# SmartWatch_System.net
KiCad netlist of a schematic drawn in EAGLE
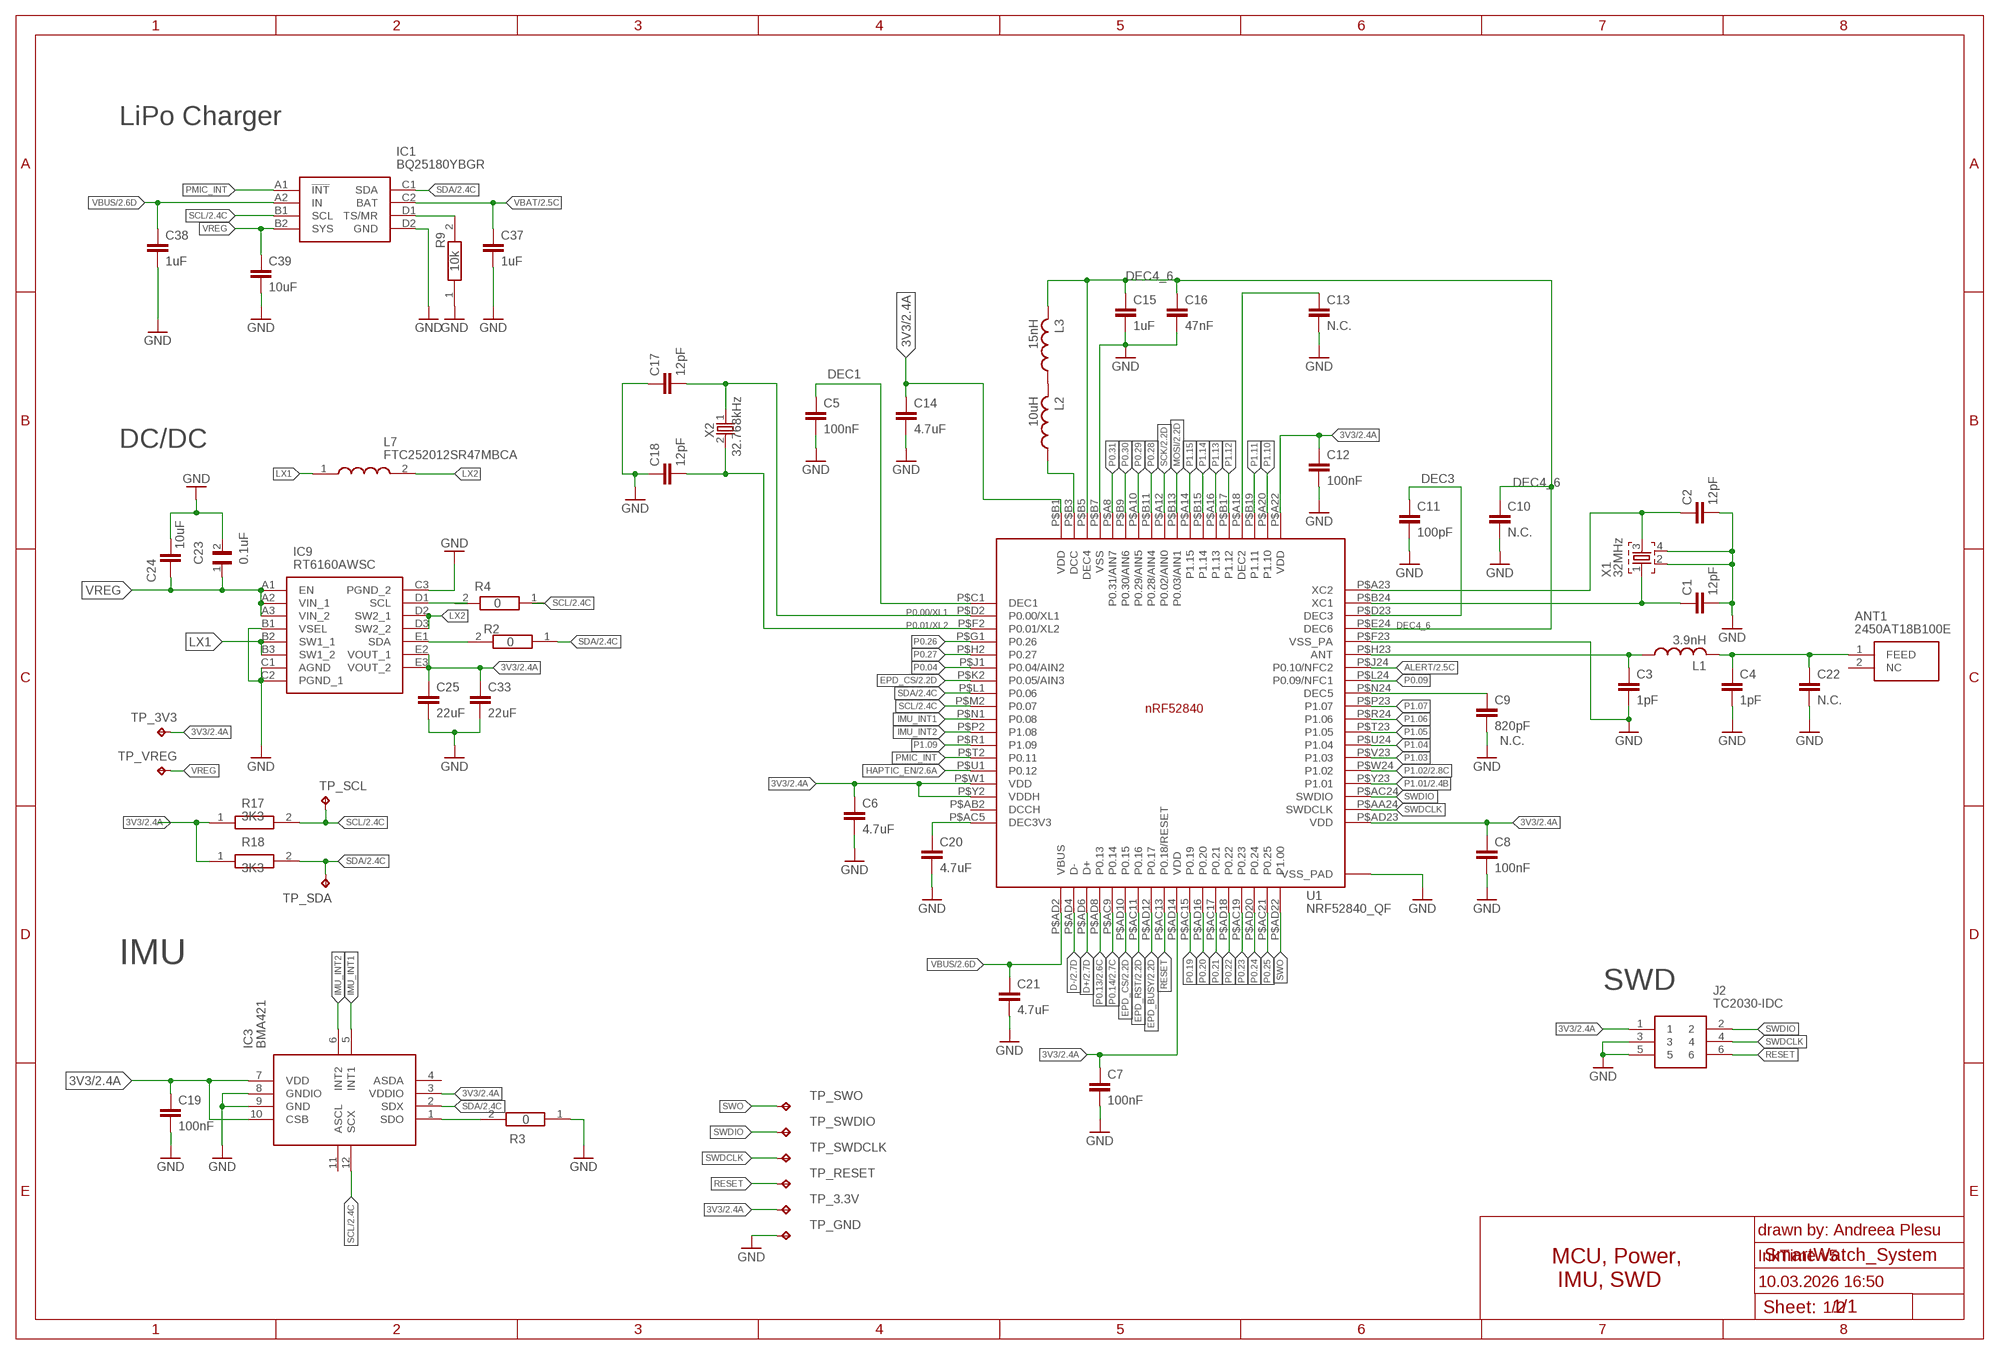
[diagram p0: schematic, sheet 1, part 1 of 2]
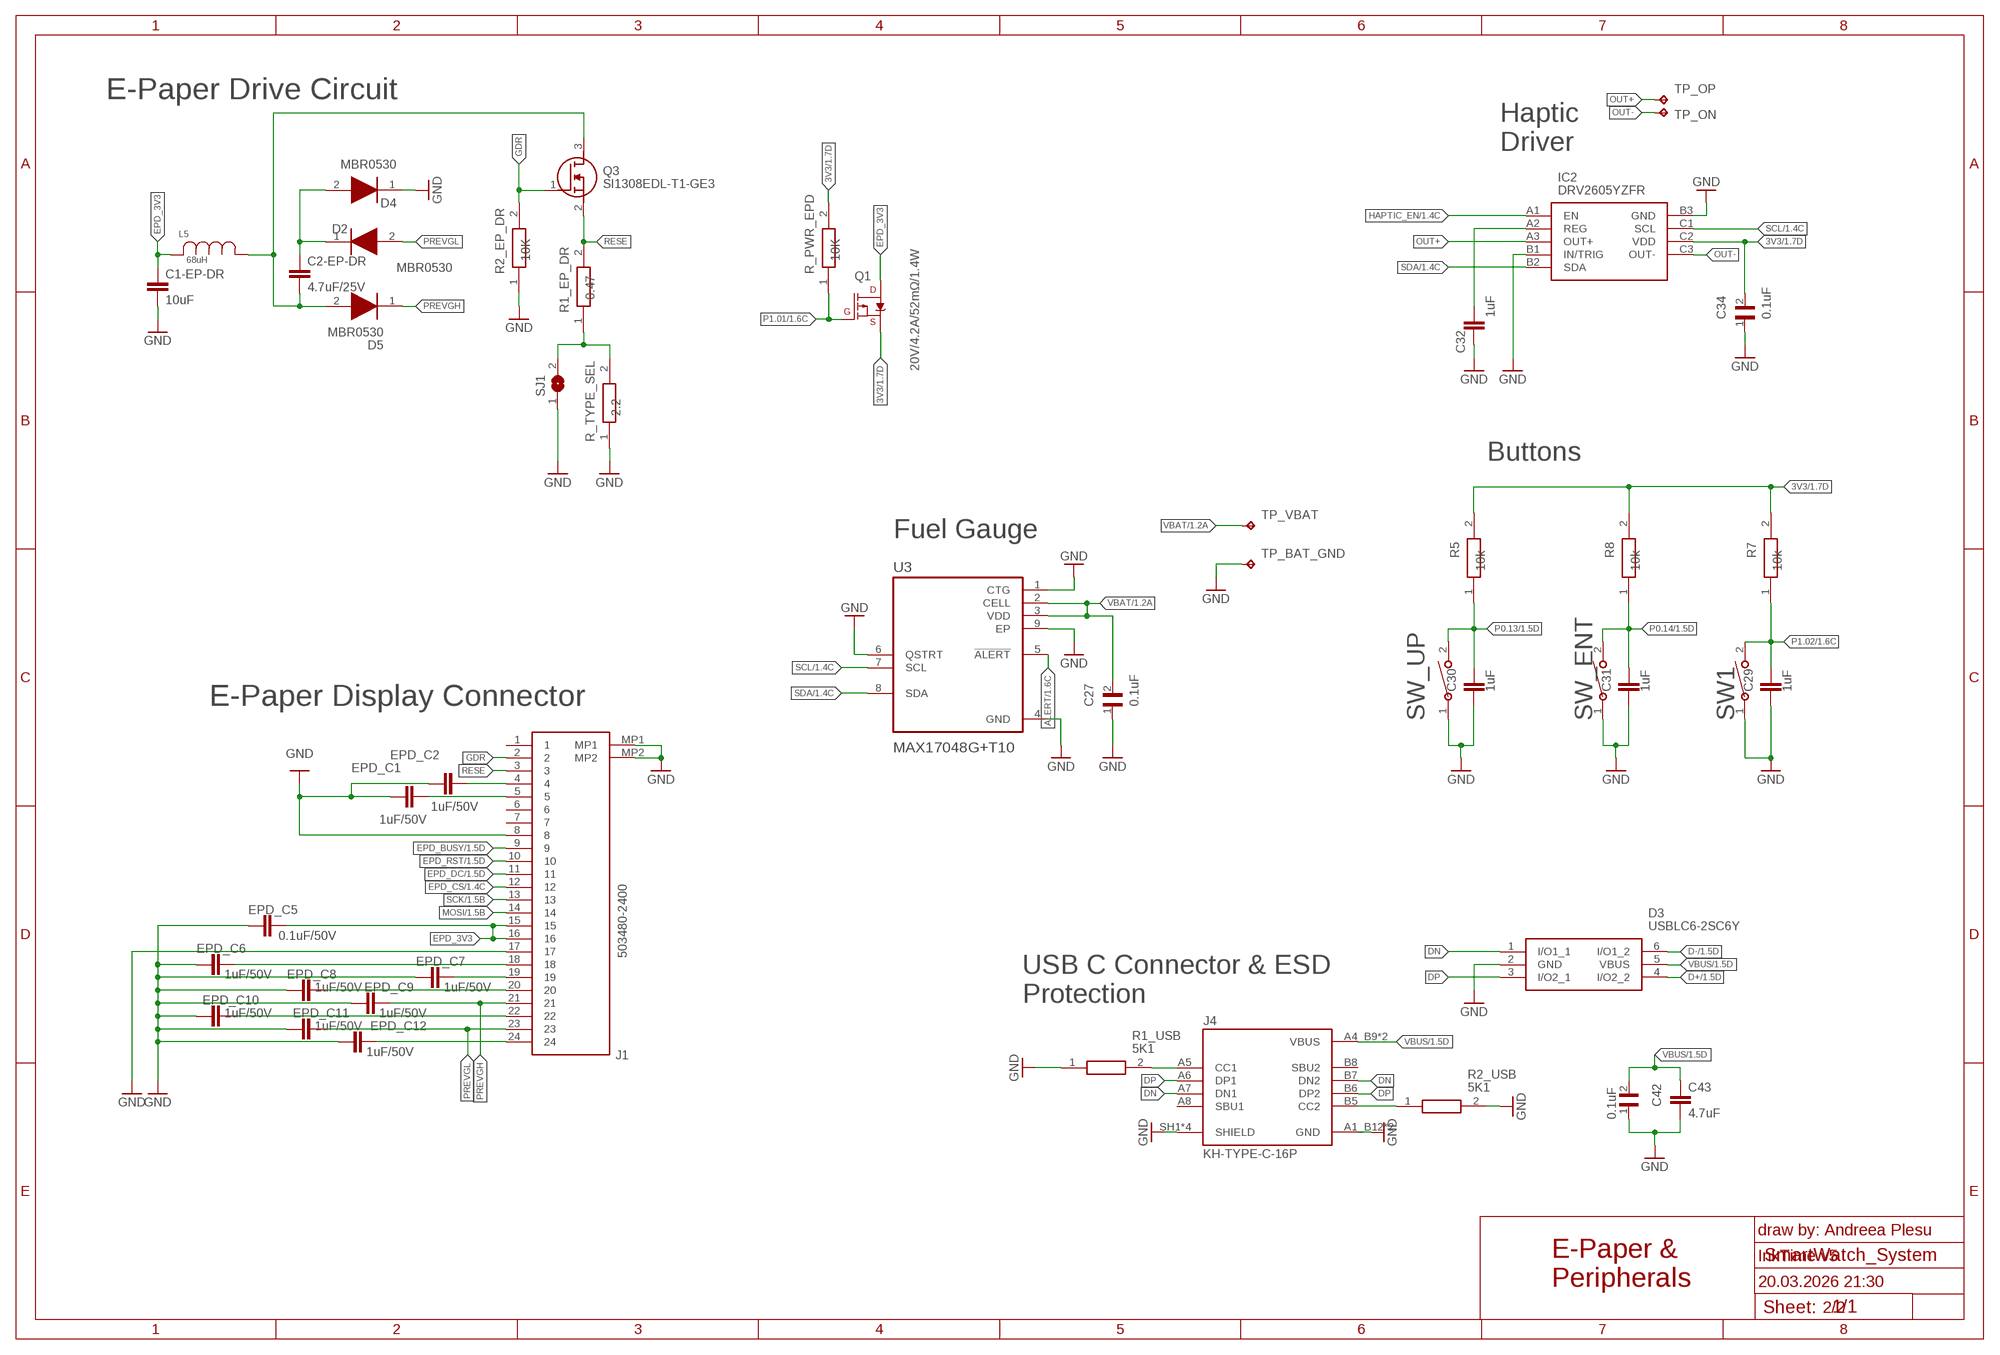
[diagram p1: schematic, sheet 1, part 2 of 2]

(export (version "E")
  (design (tool "Eeschema 10.0.6"))
  (components
    (comp (ref "ANT1")
      (value "2450AT18B100E")
      (footprint "eagle-import:2450AT18B100E_ANTC3216X140N")
      (fields (field (name "MOUSER_PART_NUMBER") "609-2450AT18B100E"))
      (libsource (lib "eagle-import") (part "2450AT18B100E_2450AT18B100E"))
    )
    (comp (ref "C1")
      (value "12pF")
      (footprint "eagle-import:NORDIC_NRF_3_RESC0201_L")
      (libsource (lib "eagle-import") (part "NORDIC_NRF_3_CAPACITOR_0201_L"))
    )
    (comp (ref "C1-EP-DR")
      (value "10uF")
      (footprint "eagle-import:NORDIC_NRF_3_RESC0402_L")
      (libsource (lib "eagle-import") (part "NORDIC_NRF_3_CAPACITOR_0402_L"))
    )
    (comp (ref "C2")
      (value "12pF")
      (footprint "eagle-import:NORDIC_NRF_3_RESC0201_L")
      (libsource (lib "eagle-import") (part "NORDIC_NRF_3_CAPACITOR_0201_L"))
    )
    (comp (ref "C2-EP-DR")
      (value "4.7uF/25V")
      (footprint "eagle-import:NORDIC_NRF_3_RESC0402_L")
      (libsource (lib "eagle-import") (part "NORDIC_NRF_3_CAPACITOR_0402_L"))
    )
    (comp (ref "C3")
      (value "1pF")
      (footprint "eagle-import:NORDIC_NRF_3_RESC0201_L")
      (libsource (lib "eagle-import") (part "NORDIC_NRF_3_CAPACITOR_0201_L"))
    )
    (comp (ref "C4")
      (value "1pF")
      (footprint "eagle-import:NORDIC_NRF_3_RESC0201_L")
      (libsource (lib "eagle-import") (part "NORDIC_NRF_3_CAPACITOR_0201_L"))
    )
    (comp (ref "C5")
      (value "100nF")
      (footprint "eagle-import:NORDIC_NRF_3_RESC0201_L")
      (libsource (lib "eagle-import") (part "NORDIC_NRF_3_CAPACITOR_0201_L"))
    )
    (comp (ref "C6")
      (value "4.7uF")
      (footprint "eagle-import:NORDIC_NRF_3_RESC0402_L")
      (libsource (lib "eagle-import") (part "NORDIC_NRF_3_CAPACITOR_0402_L"))
    )
    (comp (ref "C7")
      (value "100nF")
      (footprint "eagle-import:NORDIC_NRF_3_RESC0201_L")
      (libsource (lib "eagle-import") (part "NORDIC_NRF_3_CAPACITOR_0201_L"))
    )
    (comp (ref "C8")
      (value "100nF")
      (footprint "eagle-import:NORDIC_NRF_3_RESC0201_L")
      (libsource (lib "eagle-import") (part "NORDIC_NRF_3_CAPACITOR_0201_L"))
    )
    (comp (ref "C9")
      (value "820pF")
      (footprint "eagle-import:NORDIC_NRF_3_RESC0201_L")
      (libsource (lib "eagle-import") (part "NORDIC_NRF_3_CAPACITOR_0201_L"))
    )
    (comp (ref "C10")
      (value "N.C.")
      (footprint "eagle-import:NORDIC_NRF_3_RESC0201_L")
      (libsource (lib "eagle-import") (part "NORDIC_NRF_3_CAPACITOR_0201_L"))
    )
    (comp (ref "C11")
      (value "100pF")
      (footprint "eagle-import:NORDIC_NRF_3_RESC0201_L")
      (libsource (lib "eagle-import") (part "NORDIC_NRF_3_CAPACITOR_0201_L"))
    )
    (comp (ref "C12")
      (value "100nF")
      (footprint "eagle-import:NORDIC_NRF_3_RESC0201_L")
      (libsource (lib "eagle-import") (part "NORDIC_NRF_3_CAPACITOR_0201_L"))
    )
    (comp (ref "C13")
      (value "N.C.")
      (footprint "eagle-import:NORDIC_NRF_3_RESC0201_L")
      (libsource (lib "eagle-import") (part "NORDIC_NRF_3_CAPACITOR_0201_L"))
    )
    (comp (ref "C14")
      (value "4.7uF")
      (footprint "eagle-import:PERFECT_0402_0402")
      (libsource (lib "eagle-import") (part "PERFECT_0402_CAP_0402"))
    )
    (comp (ref "C15")
      (value "1uF")
      (footprint "eagle-import:PERFECT_0402_0402")
      (libsource (lib "eagle-import") (part "PERFECT_0402_CAP_0402"))
    )
    (comp (ref "C16")
      (value "47nF")
      (footprint "eagle-import:NORDIC_NRF_3_RESC0201_L")
      (libsource (lib "eagle-import") (part "NORDIC_NRF_3_CAPACITOR_0201_L"))
    )
    (comp (ref "C17")
      (value "12pF")
      (footprint "eagle-import:NORDIC_NRF_3_RESC0201_L")
      (libsource (lib "eagle-import") (part "NORDIC_NRF_3_CAPACITOR_0201_L"))
    )
    (comp (ref "C18")
      (value "12pF")
      (footprint "eagle-import:NORDIC_NRF_3_RESC0201_L")
      (libsource (lib "eagle-import") (part "NORDIC_NRF_3_CAPACITOR_0201_L"))
    )
    (comp (ref "C19")
      (value "100nF")
      (footprint "eagle-import:NORDIC_NRF_3_RESC0201_L")
      (libsource (lib "eagle-import") (part "NORDIC_NRF_3_CAPACITOR_0201_L"))
    )
    (comp (ref "C20")
      (value "4.7uF")
      (footprint "eagle-import:NORDIC_NRF_3_RESC0402_L")
      (libsource (lib "eagle-import") (part "NORDIC_NRF_3_CAPACITOR_0402_L"))
    )
    (comp (ref "C21")
      (value "4.7uF")
      (footprint "eagle-import:NORDIC_NRF_3_RESC0402_L")
      (libsource (lib "eagle-import") (part "NORDIC_NRF_3_CAPACITOR_0402_L"))
    )
    (comp (ref "C22")
      (value "N.C.")
      (footprint "eagle-import:NORDIC_NRF_3_RESC0201_L")
      (libsource (lib "eagle-import") (part "NORDIC_NRF_3_CAPACITOR_0201_L"))
    )
    (comp (ref "C23")
      (value "0.1uF")
      (footprint "eagle-import:GRM011R60J152KE01L_2_CAPC0201X13N")
      (fields (field (name "MF") "Murata") (field (name "MP") "GRM011R60J152KE01L"))
      (libsource (lib "eagle-import") (part "GRM011R60J152KE01L_2_GRM011R60J152KE01L"))
    )
    (comp (ref "C24")
      (value "10uF")
      (footprint "eagle-import:PERFECT_0402_0402")
      (libsource (lib "eagle-import") (part "PERFECT_0402_CAP_0402"))
    )
    (comp (ref "C25")
      (value "22uF")
      (footprint "eagle-import:NORDIC_NRF_3_RESC0402_L")
      (libsource (lib "eagle-import") (part "NORDIC_NRF_3_CAPACITOR_0402_L"))
    )
    (comp (ref "C27")
      (value "0.1uF")
      (footprint "eagle-import:GRM011R60J152KE01L_2_CAPC0201X13N")
      (fields (field (name "MF") "Murata") (field (name "MP") "GRM011R60J152KE01L"))
      (libsource (lib "eagle-import") (part "GRM011R60J152KE01L_2_GRM011R60J152KE01L"))
    )
    (comp (ref "C29")
      (value "1uF")
      (footprint "eagle-import:PERFECT_0402_0402")
      (libsource (lib "eagle-import") (part "PERFECT_0402_CAP_0402"))
    )
    (comp (ref "C30")
      (value "1uF")
      (footprint "eagle-import:PERFECT_0402_0402")
      (libsource (lib "eagle-import") (part "PERFECT_0402_CAP_0402"))
    )
    (comp (ref "C31")
      (value "1uF")
      (footprint "eagle-import:PERFECT_0402_0402")
      (libsource (lib "eagle-import") (part "PERFECT_0402_CAP_0402"))
    )
    (comp (ref "C32")
      (value "1uF")
      (footprint "eagle-import:NORDIC_NRF_3_RESC0402_L")
      (libsource (lib "eagle-import") (part "NORDIC_NRF_3_CAPACITOR_0402_L"))
    )
    (comp (ref "C33")
      (value "22uF")
      (footprint "eagle-import:NORDIC_NRF_3_RESC0402_L")
      (libsource (lib "eagle-import") (part "NORDIC_NRF_3_CAPACITOR_0402_L"))
    )
    (comp (ref "C34")
      (value "0.1uF")
      (footprint "eagle-import:NORDIC_NRF_3_RESC0201_L")
      (libsource (lib "eagle-import") (part "GRM011R60J152KE01L_1_GRM011R60J152KE01L"))
    )
    (comp (ref "C37")
      (value "1uF")
      (footprint "eagle-import:PERFECT_0402_0402")
      (libsource (lib "eagle-import") (part "PERFECT_0402_CAP_0402"))
    )
    (comp (ref "C38")
      (value "1uF")
      (footprint "eagle-import:PERFECT_0402_0402")
      (libsource (lib "eagle-import") (part "PERFECT_0402_CAP_0402"))
    )
    (comp (ref "C39")
      (value "10uF")
      (footprint "eagle-import:PERFECT_0402_0402")
      (libsource (lib "eagle-import") (part "PERFECT_0402_CAP_0402"))
    )
    (comp (ref "C42")
      (value "0.1uF")
      (footprint "eagle-import:NORDIC_NRF_3_RESC0201_L")
      (libsource (lib "eagle-import") (part "GRM011R60J152KE01L_1_GRM011R60J152KE01L"))
    )
    (comp (ref "C43")
      (value "4.7uF")
      (footprint "eagle-import:PERFECT_0402_0402")
      (libsource (lib "eagle-import") (part "PERFECT_0402_CAP_0402"))
    )
    (comp (ref "D2")
      (value "MBR0530")
      (footprint "eagle-import:ESP32_C6_LIBRARY_5_SOD3716X135N")
      (fields (field (name "MF") "ON Semiconductor"))
      (libsource (lib "eagle-import") (part "ESP32_C6_LIBRARY_5_MBR0530"))
    )
    (comp (ref "D3")
      (value "USBLC6-2SC6Y")
      (footprint "eagle-import:ESP32_C6_LIBRARY_3_SOT95P280X145-6N")
      (fields (field (name "MF") "STMicroelectronics"))
      (libsource (lib "eagle-import") (part "ESP32_C6_LIBRARY_3_USBLC6-2SC6Y"))
    )
    (comp (ref "D4")
      (value "MBR0530")
      (footprint "eagle-import:ESP32_C6_LIBRARY_5_SOD3716X135N")
      (fields (field (name "MF") "ON Semiconductor"))
      (libsource (lib "eagle-import") (part "ESP32_C6_LIBRARY_5_MBR0530"))
    )
    (comp (ref "D5")
      (value "MBR0530")
      (footprint "eagle-import:ESP32_C6_LIBRARY_5_SOD3716X135N")
      (fields (field (name "MF") "ON Semiconductor"))
      (libsource (lib "eagle-import") (part "ESP32_C6_LIBRARY_5_MBR0530"))
    )
    (comp (ref "EPD_C1")
      (value "1uF/50V")
      (footprint "eagle-import:NORDIC_NRF_3_RESC0402_L")
      (libsource (lib "eagle-import") (part "NORDIC_NRF_3_CAPACITOR_0402_L"))
    )
    (comp (ref "EPD_C2")
      (value "1uF/50V")
      (footprint "eagle-import:NORDIC_NRF_3_RESC0402_L")
      (libsource (lib "eagle-import") (part "NORDIC_NRF_3_CAPACITOR_0402_L"))
    )
    (comp (ref "EPD_C5")
      (value "0.1uF/50V")
      (footprint "eagle-import:NORDIC_NRF_3_RESC0201_L")
      (libsource (lib "eagle-import") (part "NORDIC_NRF_3_CAPACITOR_0201_L"))
    )
    (comp (ref "EPD_C6")
      (value "1uF/50V")
      (footprint "eagle-import:NORDIC_NRF_3_RESC0402_L")
      (libsource (lib "eagle-import") (part "NORDIC_NRF_3_CAPACITOR_0402_L"))
    )
    (comp (ref "EPD_C7")
      (value "1uF/50V")
      (footprint "eagle-import:NORDIC_NRF_3_RESC0402_L")
      (libsource (lib "eagle-import") (part "NORDIC_NRF_3_CAPACITOR_0402_L"))
    )
    (comp (ref "EPD_C8")
      (value "1uF/50V")
      (footprint "eagle-import:NORDIC_NRF_3_RESC0402_L")
      (libsource (lib "eagle-import") (part "NORDIC_NRF_3_CAPACITOR_0402_L"))
    )
    (comp (ref "EPD_C9")
      (value "1uF/50V")
      (footprint "eagle-import:NORDIC_NRF_3_RESC0402_L")
      (libsource (lib "eagle-import") (part "NORDIC_NRF_3_CAPACITOR_0402_L"))
    )
    (comp (ref "EPD_C10")
      (value "1uF/50V")
      (footprint "eagle-import:NORDIC_NRF_3_RESC0402_L")
      (libsource (lib "eagle-import") (part "NORDIC_NRF_3_CAPACITOR_0402_L"))
    )
    (comp (ref "EPD_C11")
      (value "1uF/50V")
      (footprint "eagle-import:NORDIC_NRF_3_RESC0402_L")
      (libsource (lib "eagle-import") (part "NORDIC_NRF_3_CAPACITOR_0402_L"))
    )
    (comp (ref "EPD_C12")
      (value "1uF/50V")
      (footprint "eagle-import:NORDIC_NRF_3_RESC0402_L")
      (libsource (lib "eagle-import") (part "NORDIC_NRF_3_CAPACITOR_0402_L"))
    )
    (comp (ref "IC1")
      (value "BQ25180YBGR")
      (footprint "eagle-import:BQ25180YBGR_BGA8C40P2X4_100X155X50")
      (fields (field (name "MOUSER_PART_NUMBER") "595-BQ25180YBGR"))
      (libsource (lib "eagle-import") (part "BQ25180YBGR_BQ25180YBGR"))
    )
    (comp (ref "IC2")
      (value "DRV2605YZFR")
      (footprint "eagle-import:DRV2605YZFR_BGA9C50P3X3_144X144X62")
      (libsource (lib "eagle-import") (part "DRV2605YZFR_DRV2605YZFR"))
    )
    (comp (ref "IC3")
      (value "BMA421")
      (footprint "eagle-import:BMA423_BMA423")
      (fields (field (name "ARROW_PART_NUMBER") "BMA423") (field (name "MOUSER_PART_NUMBER") "262-BMA423"))
      (libsource (lib "eagle-import") (part "BMA423_BMA423"))
    )
    (comp (ref "IC9")
      (value "RT6160AWSC")
      (footprint "eagle-import:RT6160AWSC_BGA15C40P3X5_140X230X60")
      (fields (field (name "MOUSER_PART_NUMBER") "835-RT6160AWSC"))
      (libsource (lib "eagle-import") (part "RT6160AWSC_RT6160AWSC"))
    )
    (comp (ref "J1")
      (value "503480-2400")
      (footprint "eagle-import:503480-2400_5034802400")
      (fields (field (name "MOUSER_PART_NUMBER") "538-503480-2400"))
      (libsource (lib "eagle-import") (part "503480-2400_503480-2400"))
    )
    (comp (ref "J2")
      (value "TC2030-IDC")
      (footprint "eagle-import:TC2030-IDC_TC2030IDC")
      (libsource (lib "eagle-import") (part "TC2030-IDC_TC2030-IDC"))
    )
    (comp (ref "J4")
      (value "KH-TYPE-C-16P")
      (footprint "eagle-import:KH-TYPE-C-16P_KINGHELM_KH-TYPE-C-16P")
      (fields (field (name "MF") "kinghelm"))
      (libsource (lib "eagle-import") (part "KH-TYPE-C-16P_KH-TYPE-C-16P"))
    )
    (comp (ref "L1")
      (value "3.9nH")
      (footprint "eagle-import:NORDIC_NRF_2_RESC0402_L")
      (libsource (lib "eagle-import") (part "NORDIC_NRF_2_INDUCTOR_0402_L"))
    )
    (comp (ref "L2")
      (value "10uH")
      (footprint "eagle-import:NORDIC_NRF_2_RESC0402_L")
      (libsource (lib "eagle-import") (part "NORDIC_NRF_2_INDUCTOR_0402_L"))
    )
    (comp (ref "L3")
      (value "15nH")
      (footprint "eagle-import:NORDIC_NRF_2_RESC0402_L")
      (libsource (lib "eagle-import") (part "NORDIC_NRF_2_INDUCTOR_0402_L"))
    )
    (comp (ref "L5")
      (value "68uH")
      (footprint "eagle-import:ESP32_C6_LIBRARY_2_IND_4828-WE-TPC_WRE")
      (fields
        (field (name "MANUFACTURER_PART_NUMBER") "744043680")
        (field (name "COPYRIGHT") "Copyright (C) 2024 Ultra Librarian. All rights reserved.")
      )
      (libsource (lib "eagle-import") (part "ESP32_C6_LIBRARY_2_744043680IND_4828-WE-TPC_WRE"))
    )
    (comp (ref "L7")
      (value "FTC252012SR47MBCA")
      (footprint "eagle-import:MLP2016SR47MT0S1_INDC2016X100N")
      (libsource (lib "eagle-import") (part "MLP2016SR47MT0S1_FTC252012SR47MBCA"))
    )
    (comp (ref "Q1")
      (value "20V/4.2A/52mΩ/1.4W")
      (footprint "eagle-import:ESP32_C6_LIBRARY_4_ESP32_C6_LIBRARY_4_ESP32_C6_LIBRARY_4_ESP32_C6_LIBRARY_4_ESP32_WROVER_SPARKFUN-DISCRETESEMI_SOT23-3")
      (libsource (lib "eagle-import") (part "ESP32_C6_LIBRARY_4_ESP32_WROVER_SPARKFUN-DISCRETESEMI_MOSFET_PCH-DMG2305UX-7"))
    )
    (comp (ref "Q3")
      (value "SI1308EDL-T1-GE3")
      (footprint "eagle-import:ESP32_C6_LIBRARY_6_SOT65P210X110-3N")
      (fields (field (name "MF") "Vishay Siliconix"))
      (libsource (lib "eagle-import") (part "ESP32_C6_LIBRARY_6_SI1308EDL-T1-GE3"))
    )
    (comp (ref "R1_EP_DR")
      (value "0.47")
      (footprint "eagle-import:CPF0201D7K68C1_0201")
      (libsource (lib "eagle-import") (part "CPF0201D7K68C1_CPF0201D7K68C1"))
    )
    (comp (ref "R1_USB")
      (value "5K1")
      (footprint "eagle-import:CPF0201D7K68C1_0201")
      (libsource (lib "eagle-import") (part "CPF0201D7K68C1_CPF0201D7K68C1"))
    )
    (comp (ref "R2")
      (value "0")
      (footprint "eagle-import:ERA-1AEB3401C_0201")
      (libsource (lib "eagle-import") (part "ERA-1AEB3401C_CPF0201D7K68C1"))
    )
    (comp (ref "R2_EP_DR")
      (value "10K")
      (footprint "eagle-import:CPF0201D7K68C1_0201")
      (libsource (lib "eagle-import") (part "CPF0201D7K68C1_CPF0201D7K68C1"))
    )
    (comp (ref "R2_USB")
      (value "5K1")
      (footprint "eagle-import:CPF0201D7K68C1_0201")
      (libsource (lib "eagle-import") (part "CPF0201D7K68C1_CPF0201D7K68C1"))
    )
    (comp (ref "R3")
      (value "0")
      (footprint "eagle-import:CPF0201D7K68C1_0201")
      (libsource (lib "eagle-import") (part "CPF0201D7K68C1_CPF0201D7K68C1"))
    )
    (comp (ref "R4")
      (value "0")
      (footprint "eagle-import:ERA-1AEB3401C_0201")
      (libsource (lib "eagle-import") (part "ERA-1AEB3401C_CPF0201D7K68C1"))
    )
    (comp (ref "R5")
      (value "10k")
      (footprint "eagle-import:CPF0201D7K68C1_0201")
      (libsource (lib "eagle-import") (part "CPF0201D7K68C1_CPF0201D7K68C1"))
    )
    (comp (ref "R7")
      (value "10k")
      (footprint "eagle-import:CPF0201D7K68C1_0201")
      (libsource (lib "eagle-import") (part "CPF0201D7K68C1_CPF0201D7K68C1"))
    )
    (comp (ref "R8")
      (value "10k")
      (footprint "eagle-import:CPF0201D7K68C1_0201")
      (libsource (lib "eagle-import") (part "CPF0201D7K68C1_CPF0201D7K68C1"))
    )
    (comp (ref "R9")
      (value "10k")
      (footprint "eagle-import:ERA-1AEB3401C_0201")
      (libsource (lib "eagle-import") (part "ERA-1AEB3401C_CPF0201D7K68C1"))
    )
    (comp (ref "R17")
      (value "3K3")
      (footprint "eagle-import:ERA-1AEB3401C_0201")
      (libsource (lib "eagle-import") (part "ERA-1AEB3401C_CPF0201D7K68C1"))
    )
    (comp (ref "R18")
      (value "3K3")
      (footprint "eagle-import:ERA-1AEB3401C_0201")
      (libsource (lib "eagle-import") (part "ERA-1AEB3401C_CPF0201D7K68C1"))
    )
    (comp (ref "R_PWR_EPD")
      (value "10K")
      (footprint "eagle-import:CPF0201D7K68C1_0201")
      (libsource (lib "eagle-import") (part "CPF0201D7K68C1_CPF0201D7K68C1"))
    )
    (comp (ref "R_TYPE_SEL")
      (value "2.2")
      (footprint "eagle-import:CPF0201D7K68C1_0201")
      (libsource (lib "eagle-import") (part "CPF0201D7K68C1_CPF0201D7K68C1"))
    )
    (comp (ref "SJ1")
      (value "ESP32_C6_LIBRARY_7_JUMPER_SJ")
      (footprint "eagle-import:ESP32_C6_LIBRARY_7_JUMPER_SJ")
      (libsource (lib "eagle-import") (part "ESP32_C6_LIBRARY_7_JUMPER_SJ"))
    )
    (comp (ref "SW1")
      (value "2025-10-22_07-23-44_LIBRARY_EVP-AKE31ASW_EVP-AKE31A_PAN")
      (footprint "eagle-import:2025-10-22_07-23-44_LIBRARY_SW_EVP-AKE31A_PAN")
      (fields
        (field (name "MANUFACTURER_PART_NUMBER") "EVP-AKE31A")
        (field (name "COPYRIGHT") "Copyright (C) 2025 Ultra Librarian. All rights reserved.")
      )
      (libsource (lib "eagle-import") (part "2025-10-22_07-23-44_LIBRARY_EVP-AKE31ASW_EVP-AKE31A_PAN"))
    )
    (comp (ref "SW_ENT")
      (value "2025-10-22_07-23-44_LIBRARY_EVP-AKE31ASW_EVP-AKE31A_PAN")
      (footprint "eagle-import:2025-10-22_07-23-44_LIBRARY_SW_EVP-AKE31A_PAN")
      (fields
        (field (name "MANUFACTURER_PART_NUMBER") "EVP-AKE31A")
        (field (name "COPYRIGHT") "Copyright (C) 2025 Ultra Librarian. All rights reserved.")
      )
      (libsource (lib "eagle-import") (part "2025-10-22_07-23-44_LIBRARY_EVP-AKE31ASW_EVP-AKE31A_PAN"))
    )
    (comp (ref "SW_UP")
      (value "2025-10-22_07-23-44_LIBRARY_EVP-AKE31ASW_EVP-AKE31A_PAN")
      (footprint "eagle-import:2025-10-22_07-23-44_LIBRARY_SW_EVP-AKE31A_PAN")
      (fields
        (field (name "MANUFACTURER_PART_NUMBER") "EVP-AKE31A")
        (field (name "COPYRIGHT") "Copyright (C) 2025 Ultra Librarian. All rights reserved.")
      )
      (libsource (lib "eagle-import") (part "2025-10-22_07-23-44_LIBRARY_EVP-AKE31ASW_EVP-AKE31A_PAN"))
    )
    (comp (ref "TP_3.3V")
      (value "HECTOR_WATCH_1_TPTP20R")
      (footprint "eagle-import:HECTOR_WATCH_1_TP20R")
      (libsource (lib "eagle-import") (part "HECTOR_WATCH_1_TPTP20R"))
    )
    (comp (ref "TP_3V3")
      (value "HECTOR_WATCH_1_TPTP20R")
      (footprint "eagle-import:HECTOR_WATCH_1_TP20R")
      (libsource (lib "eagle-import") (part "HECTOR_WATCH_1_TPTP20R"))
    )
    (comp (ref "TP_BAT_GND")
      (value "HECTOR_WATCH_1_TPTP20R")
      (footprint "eagle-import:HECTOR_WATCH_1_TP20R")
      (libsource (lib "eagle-import") (part "HECTOR_WATCH_1_TPTP20R"))
    )
    (comp (ref "TP_GND")
      (value "HECTOR_WATCH_1_TPTP20R")
      (footprint "eagle-import:HECTOR_WATCH_1_TP20R")
      (libsource (lib "eagle-import") (part "HECTOR_WATCH_1_TPTP20R"))
    )
    (comp (ref "TP_ON")
      (value "HECTOR_WATCH_1_TPTP20R")
      (footprint "eagle-import:HECTOR_WATCH_1_TP20R")
      (libsource (lib "eagle-import") (part "HECTOR_WATCH_1_TPTP20R"))
    )
    (comp (ref "TP_OP")
      (value "HECTOR_WATCH_1_TPTP20R")
      (footprint "eagle-import:HECTOR_WATCH_1_TP20R")
      (libsource (lib "eagle-import") (part "HECTOR_WATCH_1_TPTP20R"))
    )
    (comp (ref "TP_RESET")
      (value "HECTOR_WATCH_1_TPTP20R")
      (footprint "eagle-import:HECTOR_WATCH_1_TP20R")
      (libsource (lib "eagle-import") (part "HECTOR_WATCH_1_TPTP20R"))
    )
    (comp (ref "TP_SCL")
      (value "HECTOR_WATCH_1_TPTP20R")
      (footprint "eagle-import:HECTOR_WATCH_1_TP20R")
      (libsource (lib "eagle-import") (part "HECTOR_WATCH_1_TPTP20R"))
    )
    (comp (ref "TP_SDA")
      (value "HECTOR_WATCH_1_TPTP20R")
      (footprint "eagle-import:HECTOR_WATCH_1_TP20R")
      (libsource (lib "eagle-import") (part "HECTOR_WATCH_1_TPTP20R"))
    )
    (comp (ref "TP_SWDCLK")
      (value "HECTOR_WATCH_1_TPTP20R")
      (footprint "eagle-import:HECTOR_WATCH_1_TP20R")
      (libsource (lib "eagle-import") (part "HECTOR_WATCH_1_TPTP20R"))
    )
    (comp (ref "TP_SWDIO")
      (value "HECTOR_WATCH_1_TPTP20R")
      (footprint "eagle-import:HECTOR_WATCH_1_TP20R")
      (libsource (lib "eagle-import") (part "HECTOR_WATCH_1_TPTP20R"))
    )
    (comp (ref "TP_SWO")
      (value "HECTOR_WATCH_1_TPTP20R")
      (footprint "eagle-import:HECTOR_WATCH_1_TP20R")
      (libsource (lib "eagle-import") (part "HECTOR_WATCH_1_TPTP20R"))
    )
    (comp (ref "TP_VBAT")
      (value "HECTOR_WATCH_1_TPTP20R")
      (footprint "eagle-import:HECTOR_WATCH_1_TP20R")
      (libsource (lib "eagle-import") (part "HECTOR_WATCH_1_TPTP20R"))
    )
    (comp (ref "TP_VREG")
      (value "HECTOR_WATCH_1_TPTP20R")
      (footprint "eagle-import:HECTOR_WATCH_1_TP20R")
      (libsource (lib "eagle-import") (part "HECTOR_WATCH_1_TPTP20R"))
    )
    (comp (ref "U1")
      (value "NRF52840_QF")
      (footprint "eagle-import:NORDIC_NRF_4_AQFN50P700X700X85_HS-74N")
      (libsource (lib "eagle-import") (part "NORDIC_NRF_4_NRF52840_QF"))
    )
    (comp (ref "U3")
      (value "MAX17048G+T10")
      (footprint "eagle-import:ESP32_C6_LIBRARY_SON50P200X200X80-9N")
      (fields (field (name "MF") "Analog Devices"))
      (libsource (lib "eagle-import") (part "ESP32_C6_LIBRARY_MAX17048G+T10"))
    )
    (comp (ref "X1")
      (value "32MHz")
      (footprint "eagle-import:NORDIC_NRF_BT-XTAL_2016_N")
      (libsource (lib "eagle-import") (part "NORDIC_NRF_XTAL_32MHZ"))
    )
    (comp (ref "X2")
      (value "32.768kHz")
      (footprint "eagle-import:NORDIC_NRF_1_XTAL_3215_N")
      (libsource (lib "eagle-import") (part "NORDIC_NRF_1_XTAL_32KHZ"))
    )
  )
  (nets
    (net (code "1") (name "/DEC1") (class "Default")
      (node (ref "C5") (pin "1") (pinfunction "1_1") (pintype "passive"))
      (node (ref "U1") (pin "P$C1") (pinfunction "DEC1_P$C1") (pintype "power_in"))
    )
    (net (code "2") (name "/DEC3") (class "Default")
      (node (ref "C11") (pin "1") (pinfunction "1_1") (pintype "passive"))
      (node (ref "U1") (pin "P$D23") (pinfunction "DEC3_P$D23") (pintype "bidirectional"))
    )
    (net (code "3") (name "/DEC4_6") (class "Default")
      (node (ref "C10") (pin "1") (pinfunction "1_1") (pintype "passive"))
      (node (ref "C15") (pin "1") (pinfunction "1_1") (pintype "passive"))
      (node (ref "C16") (pin "1") (pinfunction "1_1") (pintype "passive"))
      (node (ref "L3") (pin "2") (pinfunction "2_2") (pintype "passive"))
      (node (ref "U1") (pin "P$B5") (pinfunction "DEC4_P$B5") (pintype "power_in"))
      (node (ref "U1") (pin "P$E24") (pinfunction "DEC6_P$E24") (pintype "bidirectional"))
    )
    (net (code "4") (name "3V3{slash}1.7D") (class "Default")
      (node (ref "C34") (pin "2") (pinfunction "2_2") (pintype "passive"))
      (node (ref "IC2") (pin "C2") (pinfunction "VDD_C2") (pintype "bidirectional"))
      (node (ref "Q1") (pin "2") (pinfunction "S_2") (pintype "bidirectional"))
      (node (ref "R5") (pin "2") (pinfunction "2_2") (pintype "bidirectional"))
      (node (ref "R7") (pin "2") (pinfunction "2_2") (pintype "bidirectional"))
      (node (ref "R8") (pin "2") (pinfunction "2_2") (pintype "bidirectional"))
      (node (ref "R_PWR_EPD") (pin "2") (pinfunction "2_2") (pintype "bidirectional"))
    )
    (net (code "5") (name "3V3{slash}2.4A") (class "Default")
      (node (ref "C12") (pin "1") (pinfunction "1_1") (pintype "passive"))
      (node (ref "C14") (pin "1") (pinfunction "1_1") (pintype "passive"))
      (node (ref "C19") (pin "1") (pinfunction "1_1") (pintype "passive"))
      (node (ref "C25") (pin "1") (pinfunction "1_1") (pintype "passive"))
      (node (ref "C33") (pin "1") (pinfunction "1_1") (pintype "passive"))
      (node (ref "C6") (pin "1") (pinfunction "1_1") (pintype "passive"))
      (node (ref "C7") (pin "1") (pinfunction "1_1") (pintype "passive"))
      (node (ref "C8") (pin "1") (pinfunction "1_1") (pintype "passive"))
      (node (ref "IC3") (pin "10") (pinfunction "CSB_10") (pintype "bidirectional"))
      (node (ref "IC3") (pin "3") (pinfunction "VDDIO_3") (pintype "bidirectional"))
      (node (ref "IC3") (pin "7") (pinfunction "VDD_7") (pintype "bidirectional"))
      (node (ref "IC9") (pin "E2") (pinfunction "VOUT_1_E2") (pintype "bidirectional"))
      (node (ref "IC9") (pin "E3") (pinfunction "VOUT_2_E3") (pintype "bidirectional"))
      (node (ref "J2") (pin "1") (pinfunction "1_1") (pintype "bidirectional"))
      (node (ref "R17") (pin "1") (pinfunction "1_1") (pintype "bidirectional"))
      (node (ref "R18") (pin "1") (pinfunction "1_1") (pintype "bidirectional"))
      (node (ref "TP_3.3V") (pin "TP") (pinfunction "TP_TP") (pintype "input"))
      (node (ref "TP_3V3") (pin "TP") (pinfunction "TP_TP") (pintype "input"))
      (node (ref "U1") (pin "P$A22") (pinfunction "VDD_P$A22") (pintype "power_in"))
      (node (ref "U1") (pin "P$AD14") (pinfunction "VDD_P$AD14") (pintype "power_in"))
      (node (ref "U1") (pin "P$AD23") (pinfunction "VDD_P$AD23") (pintype "power_in"))
      (node (ref "U1") (pin "P$B1") (pinfunction "VDD_P$B1") (pintype "power_in"))
      (node (ref "U1") (pin "P$W1") (pinfunction "VDD_P$W1") (pintype "power_in"))
      (node (ref "U1") (pin "P$Y2") (pinfunction "VDDH_P$Y2") (pintype "power_in"))
    )
    (net (code "6") (name "ALERT{slash}1.6C") (class "Default")
      (node (ref "U3") (pin "5") (pinfunction "~{ALERT}_5") (pintype "output"))
    )
    (net (code "7") (name "ALERT{slash}2.5C") (class "Default")
      (node (ref "U1") (pin "P$J24") (pinfunction "P0.10/NFC2_P$J24") (pintype "bidirectional"))
    )
    (net (code "8") (name "D+{slash}1.5D") (class "Default")
      (node (ref "D3") (pin "4") (pinfunction "I/O2_2_4") (pintype "bidirectional"))
    )
    (net (code "9") (name "D+{slash}2.7D") (class "Default")
      (node (ref "U1") (pin "P$AD6") (pinfunction "D+_P$AD6") (pintype "bidirectional"))
    )
    (net (code "10") (name "D-{slash}1.5D") (class "Default")
      (node (ref "D3") (pin "6") (pinfunction "I/O1_2_6") (pintype "bidirectional"))
    )
    (net (code "11") (name "D-{slash}2.7D") (class "Default")
      (node (ref "U1") (pin "P$AD4") (pinfunction "D-_P$AD4") (pintype "bidirectional"))
    )
    (net (code "12") (name "DN") (class "Default")
      (node (ref "D3") (pin "1") (pinfunction "I/O1_1_1") (pintype "bidirectional"))
      (node (ref "J4") (pin "A7") (pinfunction "DN1_A7") (pintype "bidirectional"))
      (node (ref "J4") (pin "B7") (pinfunction "DN2_B7") (pintype "bidirectional"))
    )
    (net (code "13") (name "DP") (class "Default")
      (node (ref "D3") (pin "3") (pinfunction "I/O2_1_3") (pintype "bidirectional"))
      (node (ref "J4") (pin "A6") (pinfunction "DP1_A6") (pintype "bidirectional"))
      (node (ref "J4") (pin "B6") (pinfunction "DP2_B6") (pintype "bidirectional"))
    )
    (net (code "14") (name "EPD_3V3") (class "Default")
      (node (ref "C1-EP-DR") (pin "1") (pinfunction "1_1") (pintype "passive"))
      (node (ref "EPD_C5") (pin "2") (pinfunction "2_2") (pintype "passive"))
      (node (ref "J1") (pin "15") (pinfunction "15_15") (pintype "bidirectional"))
      (node (ref "J1") (pin "16") (pinfunction "16_16") (pintype "bidirectional"))
      (node (ref "L5") (pin "2") (pinfunction "2_2") (pintype "passive"))
      (node (ref "Q1") (pin "3") (pinfunction "D_3") (pintype "bidirectional"))
    )
    (net (code "15") (name "EPD_BUSY{slash}1.5D") (class "Default")
      (node (ref "J1") (pin "9") (pinfunction "9_9") (pintype "bidirectional"))
    )
    (net (code "16") (name "EPD_BUSY{slash}2.2D") (class "Default")
      (node (ref "U1") (pin "P$AD12") (pinfunction "P0.17_P$AD12") (pintype "bidirectional"))
    )
    (net (code "17") (name "EPD_CS{slash}1.4C") (class "Default")
      (node (ref "J1") (pin "12") (pinfunction "12_12") (pintype "bidirectional"))
    )
    (net (code "18") (name "EPD_CS{slash}2.2D") (class "Default")
      (node (ref "U1") (pin "P$AD10") (pinfunction "P0.15_P$AD10") (pintype "bidirectional"))
      (node (ref "U1") (pin "P$K2") (pinfunction "P0.05/AIN3_P$K2") (pintype "bidirectional"))
    )
    (net (code "19") (name "EPD_DC{slash}1.5D") (class "Default")
      (node (ref "J1") (pin "11") (pinfunction "11_11") (pintype "bidirectional"))
    )
    (net (code "20") (name "EPD_RST{slash}1.5D") (class "Default")
      (node (ref "J1") (pin "10") (pinfunction "10_10") (pintype "bidirectional"))
    )
    (net (code "21") (name "EPD_RST{slash}2.2D") (class "Default")
      (node (ref "U1") (pin "P$AC11") (pinfunction "P0.16_P$AC11") (pintype "bidirectional"))
    )
    (net (code "22") (name "GDR") (class "Default")
      (node (ref "J1") (pin "2") (pinfunction "2_2") (pintype "bidirectional"))
      (node (ref "Q3") (pin "1") (pinfunction "G_1") (pintype "bidirectional"))
      (node (ref "R2_EP_DR") (pin "2") (pinfunction "2_2") (pintype "bidirectional"))
    )
    (net (code "23") (name "GND") (class "Default")
      (node (ref "C1") (pin "2") (pinfunction "2_2") (pintype "passive"))
      (node (ref "C1-EP-DR") (pin "2") (pinfunction "2_2") (pintype "passive"))
      (node (ref "C10") (pin "2") (pinfunction "2_2") (pintype "passive"))
      (node (ref "C11") (pin "2") (pinfunction "2_2") (pintype "passive"))
      (node (ref "C12") (pin "2") (pinfunction "2_2") (pintype "passive"))
      (node (ref "C13") (pin "2") (pinfunction "2_2") (pintype "passive"))
      (node (ref "C14") (pin "2") (pinfunction "2_2") (pintype "passive"))
      (node (ref "C15") (pin "2") (pinfunction "2_2") (pintype "passive"))
      (node (ref "C16") (pin "2") (pinfunction "2_2") (pintype "passive"))
      (node (ref "C17") (pin "1") (pinfunction "1_1") (pintype "passive"))
      (node (ref "C18") (pin "1") (pinfunction "1_1") (pintype "passive"))
      (node (ref "C19") (pin "2") (pinfunction "2_2") (pintype "passive"))
      (node (ref "C2") (pin "2") (pinfunction "2_2") (pintype "passive"))
      (node (ref "C20") (pin "2") (pinfunction "2_2") (pintype "passive"))
      (node (ref "C21") (pin "2") (pinfunction "2_2") (pintype "passive"))
      (node (ref "C22") (pin "2") (pinfunction "2_2") (pintype "passive"))
      (node (ref "C23") (pin "2") (pinfunction "2_2") (pintype "passive"))
      (node (ref "C24") (pin "2") (pinfunction "2_2") (pintype "passive"))
      (node (ref "C25") (pin "2") (pinfunction "2_2") (pintype "passive"))
      (node (ref "C27") (pin "1") (pinfunction "1_1") (pintype "passive"))
      (node (ref "C29") (pin "2") (pinfunction "2_2") (pintype "passive"))
      (node (ref "C3") (pin "2") (pinfunction "2_2") (pintype "passive"))
      (node (ref "C30") (pin "2") (pinfunction "2_2") (pintype "passive"))
      (node (ref "C31") (pin "2") (pinfunction "2_2") (pintype "passive"))
      (node (ref "C32") (pin "2") (pinfunction "2_2") (pintype "passive"))
      (node (ref "C33") (pin "2") (pinfunction "2_2") (pintype "passive"))
      (node (ref "C34") (pin "1") (pinfunction "1_1") (pintype "passive"))
      (node (ref "C37") (pin "2") (pinfunction "2_2") (pintype "passive"))
      (node (ref "C38") (pin "2") (pinfunction "2_2") (pintype "passive"))
      (node (ref "C39") (pin "2") (pinfunction "2_2") (pintype "passive"))
      (node (ref "C4") (pin "2") (pinfunction "2_2") (pintype "passive"))
      (node (ref "C42") (pin "1") (pinfunction "1_1") (pintype "passive"))
      (node (ref "C43") (pin "2") (pinfunction "2_2") (pintype "passive"))
      (node (ref "C5") (pin "2") (pinfunction "2_2") (pintype "passive"))
      (node (ref "C6") (pin "2") (pinfunction "2_2") (pintype "passive"))
      (node (ref "C7") (pin "2") (pinfunction "2_2") (pintype "passive"))
      (node (ref "C8") (pin "2") (pinfunction "2_2") (pintype "passive"))
      (node (ref "C9") (pin "2") (pinfunction "2_2") (pintype "passive"))
      (node (ref "D3") (pin "2") (pinfunction "GND_2") (pintype "bidirectional"))
      (node (ref "D4") (pin "1") (pinfunction "K_1") (pintype "bidirectional"))
      (node (ref "EPD_C1") (pin "1") (pinfunction "1_1") (pintype "passive"))
      (node (ref "EPD_C10") (pin "1") (pinfunction "1_1") (pintype "passive"))
      (node (ref "EPD_C11") (pin "1") (pinfunction "1_1") (pintype "passive"))
      (node (ref "EPD_C12") (pin "1") (pinfunction "1_1") (pintype "passive"))
      (node (ref "EPD_C2") (pin "1") (pinfunction "1_1") (pintype "passive"))
      (node (ref "EPD_C5") (pin "1") (pinfunction "1_1") (pintype "passive"))
      (node (ref "EPD_C6") (pin "1") (pinfunction "1_1") (pintype "passive"))
      (node (ref "EPD_C7") (pin "1") (pinfunction "1_1") (pintype "passive"))
      (node (ref "EPD_C8") (pin "1") (pinfunction "1_1") (pintype "passive"))
      (node (ref "EPD_C9") (pin "1") (pinfunction "1_1") (pintype "passive"))
      (node (ref "IC1") (pin "D2") (pinfunction "GND_D2") (pintype "bidirectional"))
      (node (ref "IC2") (pin "B1") (pinfunction "IN/TRIG_B1") (pintype "bidirectional"))
      (node (ref "IC2") (pin "B3") (pinfunction "GND_B3") (pintype "bidirectional"))
      (node (ref "IC3") (pin "8") (pinfunction "GNDIO_8") (pintype "bidirectional"))
      (node (ref "IC3") (pin "9") (pinfunction "GND_9") (pintype "bidirectional"))
      (node (ref "IC9") (pin "B1") (pinfunction "VSEL_B1") (pintype "bidirectional"))
      (node (ref "IC9") (pin "C1") (pinfunction "AGND_C1") (pintype "bidirectional"))
      (node (ref "IC9") (pin "C2") (pinfunction "PGND_1_C2") (pintype "bidirectional"))
      (node (ref "IC9") (pin "C3") (pinfunction "PGND_2_C3") (pintype "bidirectional"))
      (node (ref "J1") (pin "17") (pinfunction "17_17") (pintype "bidirectional"))
      (node (ref "J1") (pin "8") (pinfunction "8_8") (pintype "bidirectional"))
      (node (ref "J1") (pin "MP1") (pinfunction "MP1_MP1") (pintype "bidirectional"))
      (node (ref "J1") (pin "MP2") (pinfunction "MP2_MP2") (pintype "bidirectional"))
      (node (ref "J2") (pin "3") (pinfunction "3_3") (pintype "bidirectional"))
      (node (ref "J2") (pin "5") (pinfunction "5_5") (pintype "bidirectional"))
      (node (ref "J4") (pin "A12_B1") (pinfunction "GND_A12_B1") (pintype "power_in"))
      (node (ref "J4") (pin "A1_B12") (pinfunction "GND_A1_B12") (pintype "power_in"))
      (node (ref "J4") (pin "SH1") (pinfunction "SHIELD_SH1") (pintype "passive"))
      (node (ref "J4") (pin "SH2") (pinfunction "SHIELD_SH2") (pintype "passive"))
      (node (ref "J4") (pin "SH3") (pinfunction "SHIELD_SH3") (pintype "passive"))
      (node (ref "J4") (pin "SH4") (pinfunction "SHIELD_SH4") (pintype "passive"))
      (node (ref "R1_USB") (pin "1") (pinfunction "1_1") (pintype "bidirectional"))
      (node (ref "R2_EP_DR") (pin "1") (pinfunction "1_1") (pintype "bidirectional"))
      (node (ref "R2_USB") (pin "2") (pinfunction "2_2") (pintype "bidirectional"))
      (node (ref "R3") (pin "1") (pinfunction "1_1") (pintype "bidirectional"))
      (node (ref "R9") (pin "1") (pinfunction "1_1") (pintype "bidirectional"))
      (node (ref "R_TYPE_SEL") (pin "1") (pinfunction "1_1") (pintype "bidirectional"))
      (node (ref "SJ1") (pin "1") (pinfunction "1_1") (pintype "passive"))
      (node (ref "SW1") (pin "1") (pinfunction "1_1") (pintype "passive"))
      (node (ref "SW_ENT") (pin "1") (pinfunction "1_1") (pintype "passive"))
      (node (ref "SW_UP") (pin "1") (pinfunction "1_1") (pintype "passive"))
      (node (ref "TP_BAT_GND") (pin "TP") (pinfunction "TP_TP") (pintype "input"))
      (node (ref "TP_GND") (pin "TP") (pinfunction "TP_TP") (pintype "input"))
      (node (ref "U1") (pin "P$74") (pinfunction "VSS_PAD_P$74") (pintype "bidirectional"))
      (node (ref "U1") (pin "P$75") (pinfunction "VSS_PAD_P$75") (pintype "bidirectional"))
      (node (ref "U1") (pin "P$76") (pinfunction "VSS_PAD_P$76") (pintype "bidirectional"))
      (node (ref "U1") (pin "P$77") (pinfunction "VSS_PAD_P$77") (pintype "bidirectional"))
      (node (ref "U1") (pin "P$78") (pinfunction "VSS_PAD_P$78") (pintype "bidirectional"))
      (node (ref "U1") (pin "P$79") (pinfunction "VSS_PAD_P$79") (pintype "bidirectional"))
      (node (ref "U1") (pin "P$80") (pinfunction "VSS_PAD_P$80") (pintype "bidirectional"))
      (node (ref "U1") (pin "P$81") (pinfunction "VSS_PAD_P$81") (pintype "bidirectional"))
      (node (ref "U1") (pin "P$82") (pinfunction "VSS_PAD_P$82") (pintype "bidirectional"))
      (node (ref "U1") (pin "P$83") (pinfunction "VSS_PAD_P$83") (pintype "bidirectional"))
      (node (ref "U1") (pin "P$84") (pinfunction "VSS_PAD_P$84") (pintype "bidirectional"))
      (node (ref "U1") (pin "P$85") (pinfunction "VSS_PAD_P$85") (pintype "bidirectional"))
      (node (ref "U1") (pin "P$86") (pinfunction "VSS_PAD_P$86") (pintype "bidirectional"))
      (node (ref "U1") (pin "P$87") (pinfunction "VSS_PAD_P$87") (pintype "bidirectional"))
      (node (ref "U1") (pin "P$88") (pinfunction "VSS_PAD_P$88") (pintype "bidirectional"))
      (node (ref "U1") (pin "P$89") (pinfunction "VSS_PAD_P$89") (pintype "bidirectional"))
      (node (ref "U1") (pin "P$90") (pinfunction "VSS_PAD_P$90") (pintype "bidirectional"))
      (node (ref "U1") (pin "P$B7") (pinfunction "VSS_P$B7") (pintype "power_in"))
      (node (ref "U1") (pin "P$F23") (pinfunction "VSS_PA_P$F23") (pintype "bidirectional"))
      (node (ref "U3") (pin "1") (pinfunction "CTG_1") (pintype "power_in"))
      (node (ref "U3") (pin "4") (pinfunction "GND_4") (pintype "power_in"))
      (node (ref "U3") (pin "6") (pinfunction "QSTRT_6") (pintype "input"))
      (node (ref "U3") (pin "9") (pinfunction "EP_9") (pintype "power_in"))
      (node (ref "X1") (pin "2") (pinfunction "2_2") (pintype "passive"))
      (node (ref "X1") (pin "4") (pinfunction "4_4") (pintype "passive"))
    )
    (net (code "24") (name "HAPTIC_EN{slash}1.4C") (class "Default")
      (node (ref "IC2") (pin "A1") (pinfunction "EN_A1") (pintype "bidirectional"))
    )
    (net (code "25") (name "HAPTIC_EN{slash}2.6A") (class "Default")
      (node (ref "U1") (pin "P$U1") (pinfunction "P0.12_P$U1") (pintype "bidirectional"))
    )
    (net (code "26") (name "IMU_INT1") (class "Default")
      (node (ref "IC3") (pin "5") (pinfunction "INT1_5") (pintype "bidirectional"))
      (node (ref "U1") (pin "P$N1") (pinfunction "P0.08_P$N1") (pintype "bidirectional"))
    )
    (net (code "27") (name "IMU_INT2") (class "Default")
      (node (ref "IC3") (pin "6") (pinfunction "INT2_6") (pintype "bidirectional"))
      (node (ref "U1") (pin "P$P2") (pinfunction "P1.08_P$P2") (pintype "bidirectional"))
    )
    (net (code "28") (name "LX1") (class "Default")
      (node (ref "IC9") (pin "B2") (pinfunction "SW1_1_B2") (pintype "bidirectional"))
      (node (ref "IC9") (pin "B3") (pinfunction "SW1_2_B3") (pintype "bidirectional"))
      (node (ref "L7") (pin "1") (pinfunction "1_1") (pintype "bidirectional"))
    )
    (net (code "29") (name "LX2") (class "Default")
      (node (ref "IC9") (pin "D2") (pinfunction "SW2_1_D2") (pintype "bidirectional"))
      (node (ref "IC9") (pin "D3") (pinfunction "SW2_2_D3") (pintype "bidirectional"))
      (node (ref "L7") (pin "2") (pinfunction "2_2") (pintype "bidirectional"))
    )
    (net (code "30") (name "MOSI{slash}1.5B") (class "Default")
      (node (ref "J1") (pin "14") (pinfunction "14_14") (pintype "bidirectional"))
    )
    (net (code "31") (name "MOSI{slash}2.2D") (class "Default")
      (node (ref "U1") (pin "P$B13") (pinfunction "P0.03/AIN1_P$B13") (pintype "bidirectional"))
    )
    (net (code "32") (name "Net-(ANT1-FEED)") (class "Default")
      (node (ref "ANT1") (pin "1") (pinfunction "FEED_1") (pintype "input"))
      (node (ref "C22") (pin "1") (pinfunction "1_1") (pintype "passive"))
      (node (ref "C4") (pin "1") (pinfunction "1_1") (pintype "passive"))
      (node (ref "L1") (pin "2") (pinfunction "2_2") (pintype "passive"))
    )
    (net (code "33") (name "Net-(D2-K)") (class "Default")
      (node (ref "C2-EP-DR") (pin "1") (pinfunction "1_1") (pintype "passive"))
      (node (ref "D2") (pin "1") (pinfunction "K_1") (pintype "bidirectional"))
      (node (ref "D4") (pin "2") (pinfunction "A_2") (pintype "bidirectional"))
    )
    (net (code "34") (name "Net-(D5-A)") (class "Default")
      (node (ref "C2-EP-DR") (pin "2") (pinfunction "2_2") (pintype "passive"))
      (node (ref "D5") (pin "2") (pinfunction "A_2") (pintype "bidirectional"))
      (node (ref "L5") (pin "1") (pinfunction "1_1") (pintype "passive"))
      (node (ref "Q3") (pin "3") (pinfunction "D_3") (pintype "bidirectional"))
    )
    (net (code "35") (name "Net-(EPD_C1-Pad2)") (class "Default")
      (node (ref "EPD_C1") (pin "2") (pinfunction "2_2") (pintype "passive"))
      (node (ref "J1") (pin "5") (pinfunction "5_5") (pintype "bidirectional"))
    )
    (net (code "36") (name "Net-(EPD_C2-Pad2)") (class "Default")
      (node (ref "EPD_C2") (pin "2") (pinfunction "2_2") (pintype "passive"))
      (node (ref "J1") (pin "4") (pinfunction "4_4") (pintype "bidirectional"))
    )
    (net (code "37") (name "Net-(EPD_C6-Pad2)") (class "Default")
      (node (ref "EPD_C6") (pin "2") (pinfunction "2_2") (pintype "passive"))
      (node (ref "J1") (pin "18") (pinfunction "18_18") (pintype "bidirectional"))
    )
    (net (code "38") (name "Net-(EPD_C7-Pad2)") (class "Default")
      (node (ref "EPD_C7") (pin "2") (pinfunction "2_2") (pintype "passive"))
      (node (ref "J1") (pin "19") (pinfunction "19_19") (pintype "bidirectional"))
    )
    (net (code "39") (name "Net-(EPD_C8-Pad2)") (class "Default")
      (node (ref "EPD_C8") (pin "2") (pinfunction "2_2") (pintype "passive"))
      (node (ref "J1") (pin "20") (pinfunction "20_20") (pintype "bidirectional"))
    )
    (net (code "40") (name "Net-(EPD_C10-Pad2)") (class "Default")
      (node (ref "EPD_C10") (pin "2") (pinfunction "2_2") (pintype "passive"))
      (node (ref "J1") (pin "22") (pinfunction "22_22") (pintype "bidirectional"))
    )
    (net (code "41") (name "Net-(EPD_C12-Pad2)") (class "Default")
      (node (ref "EPD_C12") (pin "2") (pinfunction "2_2") (pintype "passive"))
      (node (ref "J1") (pin "24") (pinfunction "24_24") (pintype "bidirectional"))
    )
    (net (code "42") (name "Net-(IC1-TS{slash}MR)") (class "Default")
      (node (ref "IC1") (pin "D1") (pinfunction "TS/MR_D1") (pintype "bidirectional"))
      (node (ref "R9") (pin "2") (pinfunction "2_2") (pintype "bidirectional"))
    )
    (net (code "43") (name "Net-(IC2-REG)") (class "Default")
      (node (ref "C32") (pin "1") (pinfunction "1_1") (pintype "passive"))
      (node (ref "IC2") (pin "A2") (pinfunction "REG_A2") (pintype "bidirectional"))
    )
    (net (code "44") (name "Net-(IC3-SDO)") (class "Default")
      (node (ref "IC3") (pin "1") (pinfunction "SDO_1") (pintype "bidirectional"))
      (node (ref "R3") (pin "2") (pinfunction "2_2") (pintype "bidirectional"))
    )
    (net (code "45") (name "Net-(IC9-SCL)") (class "Default")
      (node (ref "IC9") (pin "D1") (pinfunction "SCL_D1") (pintype "bidirectional"))
      (node (ref "R4") (pin "2") (pinfunction "2_2") (pintype "bidirectional"))
    )
    (net (code "46") (name "Net-(IC9-SDA)") (class "Default")
      (node (ref "IC9") (pin "E1") (pinfunction "SDA_E1") (pintype "bidirectional"))
      (node (ref "R2") (pin "2") (pinfunction "2_2") (pintype "bidirectional"))
    )
    (net (code "47") (name "Net-(J4-CC1)") (class "Default")
      (node (ref "J4") (pin "A5") (pinfunction "CC1_A5") (pintype "bidirectional"))
      (node (ref "R1_USB") (pin "2") (pinfunction "2_2") (pintype "bidirectional"))
    )
    (net (code "48") (name "Net-(J4-CC2)") (class "Default")
      (node (ref "J4") (pin "B5") (pinfunction "CC2_B5") (pintype "bidirectional"))
      (node (ref "R2_USB") (pin "1") (pinfunction "1_1") (pintype "bidirectional"))
    )
    (net (code "49") (name "Net-(L2-Pad2)") (class "Default")
      (node (ref "L2") (pin "2") (pinfunction "2_2") (pintype "passive"))
      (node (ref "L3") (pin "1") (pinfunction "1_1") (pintype "passive"))
    )
    (net (code "50") (name "Net-(R1_EP_DR-Pad1)") (class "Default")
      (node (ref "R1_EP_DR") (pin "1") (pinfunction "1_1") (pintype "bidirectional"))
      (node (ref "R_TYPE_SEL") (pin "2") (pinfunction "2_2") (pintype "bidirectional"))
      (node (ref "SJ1") (pin "2") (pinfunction "2_2") (pintype "passive"))
    )
    (net (code "51") (name "Net-(U1-ANT)") (class "Default")
      (node (ref "C3") (pin "1") (pinfunction "1_1") (pintype "passive"))
      (node (ref "L1") (pin "1") (pinfunction "1_1") (pintype "passive"))
      (node (ref "U1") (pin "P$H23") (pinfunction "ANT_P$H23") (pintype "bidirectional"))
    )
    (net (code "52") (name "Net-(U1-DCC)") (class "Default")
      (node (ref "L2") (pin "1") (pinfunction "1_1") (pintype "passive"))
      (node (ref "U1") (pin "P$B3") (pinfunction "DCC_P$B3") (pintype "output"))
    )
    (net (code "53") (name "Net-(U1-DEC2)") (class "Default")
      (node (ref "C13") (pin "1") (pinfunction "1_1") (pintype "passive"))
      (node (ref "U1") (pin "P$A18") (pinfunction "DEC2_P$A18") (pintype "bidirectional"))
    )
    (net (code "54") (name "Net-(U1-DEC3V3)") (class "Default")
      (node (ref "C20") (pin "1") (pinfunction "1_1") (pintype "passive"))
      (node (ref "U1") (pin "P$AC5") (pinfunction "DEC3V3_P$AC5") (pintype "bidirectional"))
    )
    (net (code "55") (name "Net-(U1-DEC5)") (class "Default")
      (node (ref "C9") (pin "1") (pinfunction "1_1") (pintype "passive"))
      (node (ref "U1") (pin "P$N24") (pinfunction "DEC5_P$N24") (pintype "bidirectional"))
    )
    (net (code "56") (name "Net-(U1-P0.00{slash}XL1)") (class "Default")
      (node (ref "C17") (pin "2") (pinfunction "2_2") (pintype "passive"))
      (node (ref "U1") (pin "P$D2") (pinfunction "P0.00/XL1_P$D2") (pintype "bidirectional"))
      (node (ref "X2") (pin "1") (pinfunction "1_1") (pintype "passive"))
    )
    (net (code "57") (name "Net-(U1-P0.01{slash}XL2)") (class "Default")
      (node (ref "C18") (pin "2") (pinfunction "2_2") (pintype "passive"))
      (node (ref "U1") (pin "P$F2") (pinfunction "P0.01/XL2_P$F2") (pintype "bidirectional"))
      (node (ref "X2") (pin "2") (pinfunction "2_2") (pintype "passive"))
    )
    (net (code "58") (name "Net-(U1-XC1)") (class "Default")
      (node (ref "C1") (pin "1") (pinfunction "1_1") (pintype "passive"))
      (node (ref "U1") (pin "P$B24") (pinfunction "XC1_P$B24") (pintype "input"))
      (node (ref "X1") (pin "1") (pinfunction "1_1") (pintype "passive"))
    )
    (net (code "59") (name "Net-(U1-XC2)") (class "Default")
      (node (ref "C2") (pin "1") (pinfunction "1_1") (pintype "passive"))
      (node (ref "U1") (pin "P$A23") (pinfunction "XC2_P$A23") (pintype "output"))
      (node (ref "X1") (pin "3") (pinfunction "3_3") (pintype "passive"))
    )
    (net (code "60") (name "OUT+") (class "Default")
      (node (ref "IC2") (pin "A3") (pinfunction "OUT+_A3") (pintype "bidirectional"))
      (node (ref "TP_OP") (pin "TP") (pinfunction "TP_TP") (pintype "input"))
    )
    (net (code "61") (name "OUT-") (class "Default")
      (node (ref "IC2") (pin "C3") (pinfunction "OUT-_C3") (pintype "bidirectional"))
      (node (ref "TP_ON") (pin "TP") (pinfunction "TP_TP") (pintype "input"))
    )
    (net (code "62") (name "P0.04") (class "Default")
      (node (ref "U1") (pin "P$J1") (pinfunction "P0.04/AIN2_P$J1") (pintype "bidirectional"))
    )
    (net (code "63") (name "P0.09") (class "Default")
      (node (ref "U1") (pin "P$L24") (pinfunction "P0.09/NFC1_P$L24") (pintype "bidirectional"))
    )
    (net (code "64") (name "P0.13{slash}1.5D") (class "Default")
      (node (ref "C30") (pin "1") (pinfunction "1_1") (pintype "passive"))
      (node (ref "R5") (pin "1") (pinfunction "1_1") (pintype "bidirectional"))
      (node (ref "SW_UP") (pin "2") (pinfunction "2_2") (pintype "passive"))
    )
    (net (code "65") (name "P0.13{slash}2.6C") (class "Default")
      (node (ref "U1") (pin "P$AD8") (pinfunction "P0.13_P$AD8") (pintype "bidirectional"))
    )
    (net (code "66") (name "P0.14{slash}1.5D") (class "Default")
      (node (ref "C31") (pin "1") (pinfunction "1_1") (pintype "passive"))
      (node (ref "R8") (pin "1") (pinfunction "1_1") (pintype "bidirectional"))
      (node (ref "SW_ENT") (pin "2") (pinfunction "2_2") (pintype "passive"))
    )
    (net (code "67") (name "P0.14{slash}2.7C") (class "Default")
      (node (ref "U1") (pin "P$AC9") (pinfunction "P0.14_P$AC9") (pintype "bidirectional"))
    )
    (net (code "68") (name "P0.19") (class "Default")
      (node (ref "U1") (pin "P$AC15") (pinfunction "P0.19_P$AC15") (pintype "bidirectional"))
    )
    (net (code "69") (name "P0.20") (class "Default")
      (node (ref "U1") (pin "P$AD16") (pinfunction "P0.20_P$AD16") (pintype "bidirectional"))
    )
    (net (code "70") (name "P0.21") (class "Default")
      (node (ref "U1") (pin "P$AC17") (pinfunction "P0.21_P$AC17") (pintype "bidirectional"))
    )
    (net (code "71") (name "P0.22") (class "Default")
      (node (ref "U1") (pin "P$AD18") (pinfunction "P0.22_P$AD18") (pintype "bidirectional"))
    )
    (net (code "72") (name "P0.23") (class "Default")
      (node (ref "U1") (pin "P$AC19") (pinfunction "P0.23_P$AC19") (pintype "bidirectional"))
    )
    (net (code "73") (name "P0.24") (class "Default")
      (node (ref "U1") (pin "P$AD20") (pinfunction "P0.24_P$AD20") (pintype "bidirectional"))
    )
    (net (code "74") (name "P0.25") (class "Default")
      (node (ref "U1") (pin "P$AC21") (pinfunction "P0.25_P$AC21") (pintype "bidirectional"))
    )
    (net (code "75") (name "P0.26") (class "Default")
      (node (ref "U1") (pin "P$G1") (pinfunction "P0.26_P$G1") (pintype "bidirectional"))
    )
    (net (code "76") (name "P0.27") (class "Default")
      (node (ref "U1") (pin "P$H2") (pinfunction "P0.27_P$H2") (pintype "bidirectional"))
    )
    (net (code "77") (name "P0.28") (class "Default")
      (node (ref "U1") (pin "P$B11") (pinfunction "P0.28/AIN4_P$B11") (pintype "bidirectional"))
    )
    (net (code "78") (name "P0.29") (class "Default")
      (node (ref "U1") (pin "P$A10") (pinfunction "P0.29/AIN5_P$A10") (pintype "bidirectional"))
    )
    (net (code "79") (name "P0.30") (class "Default")
      (node (ref "U1") (pin "P$B9") (pinfunction "P0.30/AIN6_P$B9") (pintype "bidirectional"))
    )
    (net (code "80") (name "P0.31") (class "Default")
      (node (ref "U1") (pin "P$A8") (pinfunction "P0.31/AIN7_P$A8") (pintype "bidirectional"))
    )
    (net (code "81") (name "P1.01{slash}1.6C") (class "Default")
      (node (ref "Q1") (pin "1") (pinfunction "G_1") (pintype "bidirectional"))
      (node (ref "R_PWR_EPD") (pin "1") (pinfunction "1_1") (pintype "bidirectional"))
    )
    (net (code "82") (name "P1.01{slash}2.4B") (class "Default")
      (node (ref "U1") (pin "P$Y23") (pinfunction "P1.01_P$Y23") (pintype "bidirectional"))
    )
    (net (code "83") (name "P1.02{slash}1.6C") (class "Default")
      (node (ref "C29") (pin "1") (pinfunction "1_1") (pintype "passive"))
      (node (ref "R7") (pin "1") (pinfunction "1_1") (pintype "bidirectional"))
      (node (ref "SW1") (pin "2") (pinfunction "2_2") (pintype "passive"))
    )
    (net (code "84") (name "P1.02{slash}2.8C") (class "Default")
      (node (ref "U1") (pin "P$W24") (pinfunction "P1.02_P$W24") (pintype "bidirectional"))
    )
    (net (code "85") (name "P1.03") (class "Default")
      (node (ref "U1") (pin "P$V23") (pinfunction "P1.03_P$V23") (pintype "bidirectional"))
    )
    (net (code "86") (name "P1.04") (class "Default")
      (node (ref "U1") (pin "P$U24") (pinfunction "P1.04_P$U24") (pintype "bidirectional"))
    )
    (net (code "87") (name "P1.05") (class "Default")
      (node (ref "U1") (pin "P$T23") (pinfunction "P1.05_P$T23") (pintype "bidirectional"))
    )
    (net (code "88") (name "P1.06") (class "Default")
      (node (ref "U1") (pin "P$R24") (pinfunction "P1.06_P$R24") (pintype "bidirectional"))
    )
    (net (code "89") (name "P1.07") (class "Default")
      (node (ref "U1") (pin "P$P23") (pinfunction "P1.07_P$P23") (pintype "bidirectional"))
    )
    (net (code "90") (name "P1.09") (class "Default")
      (node (ref "U1") (pin "P$R1") (pinfunction "P1.09_P$R1") (pintype "bidirectional"))
    )
    (net (code "91") (name "P1.10") (class "Default")
      (node (ref "U1") (pin "P$A20") (pinfunction "P1.10_P$A20") (pintype "bidirectional"))
    )
    (net (code "92") (name "P1.11") (class "Default")
      (node (ref "U1") (pin "P$B19") (pinfunction "P1.11_P$B19") (pintype "bidirectional"))
    )
    (net (code "93") (name "P1.12") (class "Default")
      (node (ref "U1") (pin "P$B17") (pinfunction "P1.12_P$B17") (pintype "bidirectional"))
    )
    (net (code "94") (name "P1.13") (class "Default")
      (node (ref "U1") (pin "P$A16") (pinfunction "P1.13_P$A16") (pintype "bidirectional"))
    )
    (net (code "95") (name "P1.14") (class "Default")
      (node (ref "U1") (pin "P$B15") (pinfunction "P1.14_P$B15") (pintype "bidirectional"))
    )
    (net (code "96") (name "P1.15") (class "Default")
      (node (ref "U1") (pin "P$A14") (pinfunction "P1.15_P$A14") (pintype "bidirectional"))
    )
    (net (code "97") (name "PMIC_INT") (class "Default")
      (node (ref "IC1") (pin "A1") (pinfunction "~{INT}_A1") (pintype "bidirectional"))
      (node (ref "U1") (pin "P$T2") (pinfunction "P0.11_P$T2") (pintype "bidirectional"))
    )
    (net (code "98") (name "PREVGH") (class "Default")
      (node (ref "D5") (pin "1") (pinfunction "K_1") (pintype "bidirectional"))
      (node (ref "EPD_C9") (pin "2") (pinfunction "2_2") (pintype "passive"))
      (node (ref "J1") (pin "21") (pinfunction "21_21") (pintype "bidirectional"))
    )
    (net (code "99") (name "PREVGL") (class "Default")
      (node (ref "D2") (pin "2") (pinfunction "A_2") (pintype "bidirectional"))
      (node (ref "EPD_C11") (pin "2") (pinfunction "2_2") (pintype "passive"))
      (node (ref "J1") (pin "23") (pinfunction "23_23") (pintype "bidirectional"))
    )
    (net (code "100") (name "RESE") (class "Default")
      (node (ref "J1") (pin "3") (pinfunction "3_3") (pintype "bidirectional"))
      (node (ref "Q3") (pin "2") (pinfunction "S_2") (pintype "bidirectional"))
      (node (ref "R1_EP_DR") (pin "2") (pinfunction "2_2") (pintype "bidirectional"))
    )
    (net (code "101") (name "RESET") (class "Default")
      (node (ref "J2") (pin "6") (pinfunction "6_6") (pintype "bidirectional"))
      (node (ref "TP_RESET") (pin "TP") (pinfunction "TP_TP") (pintype "input"))
      (node (ref "U1") (pin "P$AC13") (pinfunction "P0.18/RESET_P$AC13") (pintype "bidirectional"))
    )
    (net (code "102") (name "SCK{slash}1.5B") (class "Default")
      (node (ref "J1") (pin "13") (pinfunction "13_13") (pintype "bidirectional"))
    )
    (net (code "103") (name "SCK{slash}2.2D") (class "Default")
      (node (ref "U1") (pin "P$A12") (pinfunction "P0.02/AIN0_P$A12") (pintype "bidirectional"))
    )
    (net (code "104") (name "SCL{slash}1.4C") (class "Default")
      (node (ref "IC2") (pin "C1") (pinfunction "SCL_C1") (pintype "bidirectional"))
      (node (ref "U3") (pin "7") (pinfunction "SCL_7") (pintype "input"))
    )
    (net (code "105") (name "SCL{slash}2.4C") (class "Default")
      (node (ref "IC1") (pin "B1") (pinfunction "SCL_B1") (pintype "bidirectional"))
      (node (ref "IC3") (pin "12") (pinfunction "SCX_12") (pintype "bidirectional"))
      (node (ref "R17") (pin "2") (pinfunction "2_2") (pintype "bidirectional"))
      (node (ref "R4") (pin "1") (pinfunction "1_1") (pintype "bidirectional"))
      (node (ref "TP_SCL") (pin "TP") (pinfunction "TP_TP") (pintype "input"))
      (node (ref "U1") (pin "P$M2") (pinfunction "P0.07_P$M2") (pintype "bidirectional"))
    )
    (net (code "106") (name "SDA{slash}1.4C") (class "Default")
      (node (ref "IC2") (pin "B2") (pinfunction "SDA_B2") (pintype "bidirectional"))
      (node (ref "U3") (pin "8") (pinfunction "SDA_8") (pintype "bidirectional"))
    )
    (net (code "107") (name "SDA{slash}2.4C") (class "Default")
      (node (ref "IC1") (pin "C1") (pinfunction "SDA_C1") (pintype "bidirectional"))
      (node (ref "IC3") (pin "2") (pinfunction "SDX_2") (pintype "bidirectional"))
      (node (ref "R18") (pin "2") (pinfunction "2_2") (pintype "bidirectional"))
      (node (ref "R2") (pin "1") (pinfunction "1_1") (pintype "bidirectional"))
      (node (ref "TP_SDA") (pin "TP") (pinfunction "TP_TP") (pintype "input"))
      (node (ref "U1") (pin "P$L1") (pinfunction "P0.06_P$L1") (pintype "bidirectional"))
    )
    (net (code "108") (name "SWDCLK") (class "Default")
      (node (ref "J2") (pin "4") (pinfunction "4_4") (pintype "bidirectional"))
      (node (ref "TP_SWDCLK") (pin "TP") (pinfunction "TP_TP") (pintype "input"))
      (node (ref "U1") (pin "P$AA24") (pinfunction "SWDCLK_P$AA24") (pintype "input"))
    )
    (net (code "109") (name "SWDIO") (class "Default")
      (node (ref "J2") (pin "2") (pinfunction "2_2") (pintype "bidirectional"))
      (node (ref "TP_SWDIO") (pin "TP") (pinfunction "TP_TP") (pintype "input"))
      (node (ref "U1") (pin "P$AC24") (pinfunction "SWDIO_P$AC24") (pintype "bidirectional"))
    )
    (net (code "110") (name "SWO") (class "Default")
      (node (ref "TP_SWO") (pin "TP") (pinfunction "TP_TP") (pintype "input"))
      (node (ref "U1") (pin "P$AD22") (pinfunction "P1.00_P$AD22") (pintype "bidirectional"))
    )
    (net (code "111") (name "VBAT{slash}1.2A") (class "Default")
      (node (ref "C27") (pin "2") (pinfunction "2_2") (pintype "passive"))
      (node (ref "TP_VBAT") (pin "TP") (pinfunction "TP_TP") (pintype "input"))
      (node (ref "U3") (pin "2") (pinfunction "CELL_2") (pintype "power_in"))
      (node (ref "U3") (pin "3") (pinfunction "VDD_3") (pintype "power_in"))
    )
    (net (code "112") (name "VBAT{slash}2.5C") (class "Default")
      (node (ref "C37") (pin "1") (pinfunction "1_1") (pintype "passive"))
      (node (ref "IC1") (pin "C2") (pinfunction "BAT_C2") (pintype "bidirectional"))
    )
    (net (code "113") (name "VBUS{slash}1.5D") (class "Default")
      (node (ref "C42") (pin "2") (pinfunction "2_2") (pintype "passive"))
      (node (ref "C43") (pin "1") (pinfunction "1_1") (pintype "passive"))
      (node (ref "D3") (pin "5") (pinfunction "VBUS_5") (pintype "bidirectional"))
      (node (ref "J4") (pin "A4_B9") (pinfunction "VBUS_A4_B9") (pintype "power_in"))
      (node (ref "J4") (pin "A9_B4") (pinfunction "VBUS_A9_B4") (pintype "power_in"))
    )
    (net (code "114") (name "VBUS{slash}2.6D") (class "Default")
      (node (ref "C21") (pin "1") (pinfunction "1_1") (pintype "passive"))
      (node (ref "C38") (pin "1") (pinfunction "1_1") (pintype "passive"))
      (node (ref "IC1") (pin "A2") (pinfunction "IN_A2") (pintype "bidirectional"))
      (node (ref "U1") (pin "P$AD2") (pinfunction "VBUS_P$AD2") (pintype "power_in"))
    )
    (net (code "115") (name "VREG") (class "Default")
      (node (ref "C23") (pin "1") (pinfunction "1_1") (pintype "passive"))
      (node (ref "C24") (pin "1") (pinfunction "1_1") (pintype "passive"))
      (node (ref "C39") (pin "1") (pinfunction "1_1") (pintype "passive"))
      (node (ref "IC1") (pin "B2") (pinfunction "SYS_B2") (pintype "bidirectional"))
      (node (ref "IC9") (pin "A1") (pinfunction "EN_A1") (pintype "bidirectional"))
      (node (ref "IC9") (pin "A2") (pinfunction "VIN_1_A2") (pintype "bidirectional"))
      (node (ref "IC9") (pin "A3") (pinfunction "VIN_2_A3") (pintype "bidirectional"))
      (node (ref "TP_VREG") (pin "TP") (pinfunction "TP_TP") (pintype "input"))
    )
    (net (code "116") (name "unconnected-(ANT1-NC-Pad2)") (class "Default")
      (node (ref "ANT1") (pin "2") (pinfunction "NC_2") (pintype "no_connect"))
    )
    (net (code "117") (name "unconnected-(IC3-ASCL-Pad11)") (class "Default")
      (node (ref "IC3") (pin "11") (pinfunction "ASCL_11") (pintype "bidirectional"))
    )
    (net (code "118") (name "unconnected-(IC3-ASDA-Pad4)") (class "Default")
      (node (ref "IC3") (pin "4") (pinfunction "ASDA_4") (pintype "bidirectional"))
    )
    (net (code "119") (name "unconnected-(J1-Pad1)") (class "Default")
      (node (ref "J1") (pin "1") (pinfunction "1_1") (pintype "bidirectional"))
    )
    (net (code "120") (name "unconnected-(J1-Pad6)") (class "Default")
      (node (ref "J1") (pin "6") (pinfunction "6_6") (pintype "bidirectional"))
    )
    (net (code "121") (name "unconnected-(J1-Pad7)") (class "Default")
      (node (ref "J1") (pin "7") (pinfunction "7_7") (pintype "bidirectional"))
    )
    (net (code "122") (name "unconnected-(J4-SBU1-PadA8)") (class "Default")
      (node (ref "J4") (pin "A8") (pinfunction "SBU1_A8") (pintype "bidirectional"))
    )
    (net (code "123") (name "unconnected-(J4-SBU2-PadB8)") (class "Default")
      (node (ref "J4") (pin "B8") (pinfunction "SBU2_B8") (pintype "bidirectional"))
    )
    (net (code "124") (name "unconnected-(U1-DCCH-PadP$AB2)") (class "Default")
      (node (ref "U1") (pin "P$AB2") (pinfunction "DCCH_P$AB2") (pintype "bidirectional"))
    )
  )
)
